# CAN.net
KiCad netlist of a schematic drawn in Altium Designer
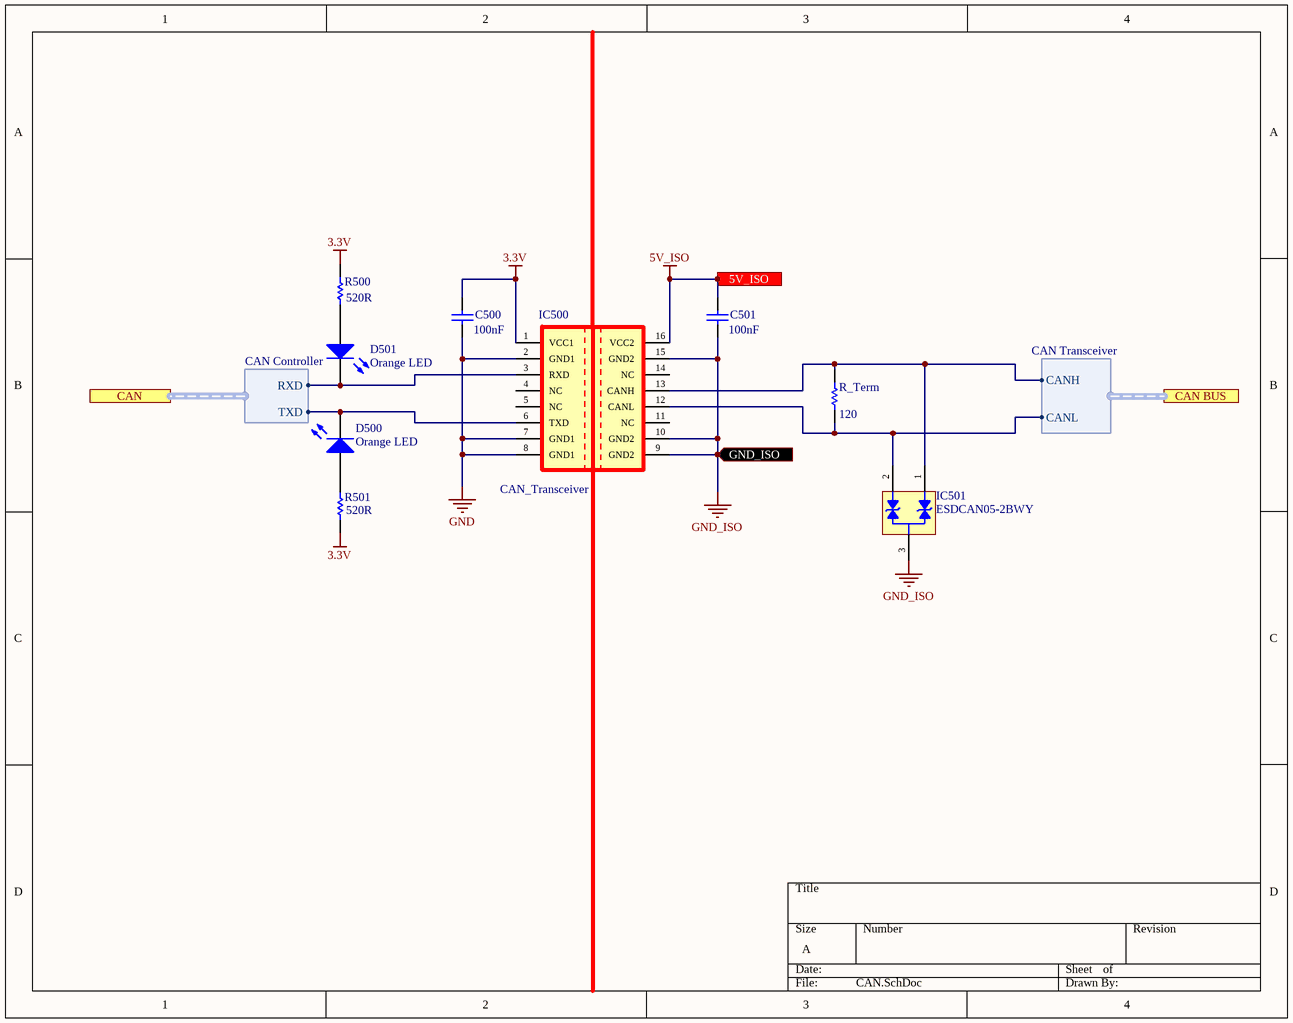
[diagram p0: CAN.SchDoc]

(export (version "E")
  (design (tool "Eeschema 10.0.6"))
  (components
    (comp (ref "C500")
      (value "100nF")
      (footprint "RAD-0.3")
      (description "Capacitor")
      (fields (field (name "Comment") "Cap") (field (name "PUBLISHER") "Altium Limited"))
      (libsource (lib "Miscellaneous Devices") (part "Cap"))
    )
    (comp (ref "C501")
      (value "100nF")
      (footprint "RAD-0.3")
      (description "Capacitor")
      (fields (field (name "Comment") "Cap") (field (name "PUBLISHER") "Altium Limited"))
      (libsource (lib "Miscellaneous Devices") (part "Cap"))
    )
    (comp (ref "D500")
      (value "Orange LED")
      (footprint "LED-0")
      (description "Typical INFRARED GaAs LED")
      (fields (field (name "PUBLISHER") "Altium Limited"))
      (libsource (lib "Miscellaneous Devices") (part "LED0"))
    )
    (comp (ref "D501")
      (value "Orange LED")
      (footprint "LED-0")
      (description "Typical INFRARED GaAs LED")
      (fields (field (name "PUBLISHER") "Altium Limited"))
      (libsource (lib "Miscellaneous Devices") (part "LED0"))
    )
    (comp (ref "IC500")
      (value "CAN_Transceiver")
      (footprint "SOIC127P1030X265-16N")
      (description "Digital Isolators Isolated 5V CAN Xcvr")
      (libsource (lib "CAN_Transceiver") (part "ISO1050DWR"))
    )
    (comp (ref "IC501")
      (value "ESDCAN05-2BWY")
      (footprint "SOT70P210X110-3N")
      (description "Automotive dual-line TVS in SOT323-3L for CAN bus")
      (libsource (lib "ESDCAN05-2BWY") (part "ESDCAN05-2BWY"))
    )
    (comp (ref "R500")
      (value "520R")
      (footprint "AXIAL-0.3")
      (description "Resistor")
      (fields (field (name "Comment") "Res1") (field (name "PUBLISHER") "Altium Limited"))
      (libsource (lib "Miscellaneous Devices") (part "Res1"))
    )
    (comp (ref "R501")
      (value "520R")
      (footprint "AXIAL-0.3")
      (description "Resistor")
      (fields (field (name "Comment") "Res1") (field (name "PUBLISHER") "Altium Limited"))
      (libsource (lib "Miscellaneous Devices") (part "Res1"))
    )
    (comp (ref "R_Term")
      (value "120")
      (footprint "AXIAL-0.3")
      (description "Resistor")
      (fields (field (name "Comment") "Res1") (field (name "PUBLISHER") "Altium Limited"))
      (libsource (lib "Miscellaneous Devices") (part "Res1"))
    )
  )
  (nets
    (net (code "6") (name "3.3V") (class "Default")
      (node (ref "C500") (pin "2") (pinfunction "2_2") (pintype "passive"))
      (node (ref "IC500") (pin "1") (pinfunction "VCC1_1") (pintype "passive"))
      (node (ref "R500") (pin "2") (pinfunction "2_2") (pintype "passive"))
      (node (ref "R501") (pin "2") (pinfunction "2_2") (pintype "passive"))
    )
    (net (code "7") (name "5V_ISO") (class "Default")
      (node (ref "C501") (pin "2") (pinfunction "2_2") (pintype "passive"))
      (node (ref "IC500") (pin "16") (pinfunction "VCC2_16") (pintype "passive"))
    )
    (net (code "8") (name "GND") (class "Default")
      (node (ref "C500") (pin "1") (pinfunction "1_1") (pintype "passive"))
      (node (ref "IC500") (pin "2") (pinfunction "GND1_2") (pintype "passive"))
      (node (ref "IC500") (pin "7") (pinfunction "GND1_7") (pintype "passive"))
      (node (ref "IC500") (pin "8") (pinfunction "GND1_8") (pintype "passive"))
    )
    (net (code "9") (name "GND_ISO") (class "Default")
      (node (ref "C501") (pin "1") (pinfunction "1_1") (pintype "passive"))
      (node (ref "IC500") (pin "10") (pinfunction "GND2_10") (pintype "passive"))
      (node (ref "IC500") (pin "15") (pinfunction "GND2_15") (pintype "passive"))
      (node (ref "IC500") (pin "9") (pinfunction "GND2_9") (pintype "passive"))
      (node (ref "IC501") (pin "3") (pinfunction "3_3") (pintype "passive"))
    )
    (net (code "10") (name "Net-(D500-A)") (class "Default")
      (node (ref "D500") (pin "1") (pinfunction "A_1") (pintype "passive"))
      (node (ref "R501") (pin "1") (pinfunction "1_1") (pintype "passive"))
    )
    (net (code "11") (name "Net-(D500-K)") (class "Default")
      (node (ref "D500") (pin "2") (pinfunction "K_2") (pintype "passive"))
      (node (ref "IC500") (pin "6") (pinfunction "TXD_6") (pintype "passive"))
    )
    (net (code "12") (name "Net-(D501-A)") (class "Default")
      (node (ref "D501") (pin "1") (pinfunction "A_1") (pintype "passive"))
      (node (ref "R500") (pin "1") (pinfunction "1_1") (pintype "passive"))
    )
    (net (code "13") (name "Net-(D501-K)") (class "Default")
      (node (ref "D501") (pin "2") (pinfunction "K_2") (pintype "passive"))
      (node (ref "IC500") (pin "3") (pinfunction "RXD_3") (pintype "passive"))
    )
    (net (code "14") (name "Net-(IC500-CANH)") (class "Default")
      (node (ref "IC500") (pin "13") (pinfunction "CANH_13") (pintype "passive"))
      (node (ref "IC501") (pin "1") (pinfunction "1_1") (pintype "passive"))
      (node (ref "R_Term") (pin "2") (pinfunction "2_2") (pintype "passive"))
    )
    (net (code "15") (name "Net-(IC500-CANL)") (class "Default")
      (node (ref "IC500") (pin "12") (pinfunction "CANL_12") (pintype "passive"))
      (node (ref "IC501") (pin "2") (pinfunction "2_2") (pintype "passive"))
      (node (ref "R_Term") (pin "1") (pinfunction "1_1") (pintype "passive"))
    )
    (net (code "16") (name "unconnected-(IC500-NC-Pad4)") (class "Default")
      (node (ref "IC500") (pin "4") (pinfunction "NC_4") (pintype "passive"))
    )
    (net (code "17") (name "unconnected-(IC500-NC-Pad5)") (class "Default")
      (node (ref "IC500") (pin "5") (pinfunction "NC_5") (pintype "passive"))
    )
    (net (code "18") (name "unconnected-(IC500-NC-Pad11)") (class "Default")
      (node (ref "IC500") (pin "11") (pinfunction "NC_11") (pintype "passive"))
    )
    (net (code "19") (name "unconnected-(IC500-NC-Pad14)") (class "Default")
      (node (ref "IC500") (pin "14") (pinfunction "NC_14") (pintype "passive"))
    )
  )
)
